# qo-100-env-sensors.net
KiCad netlist of a schematic drawn in EAGLE
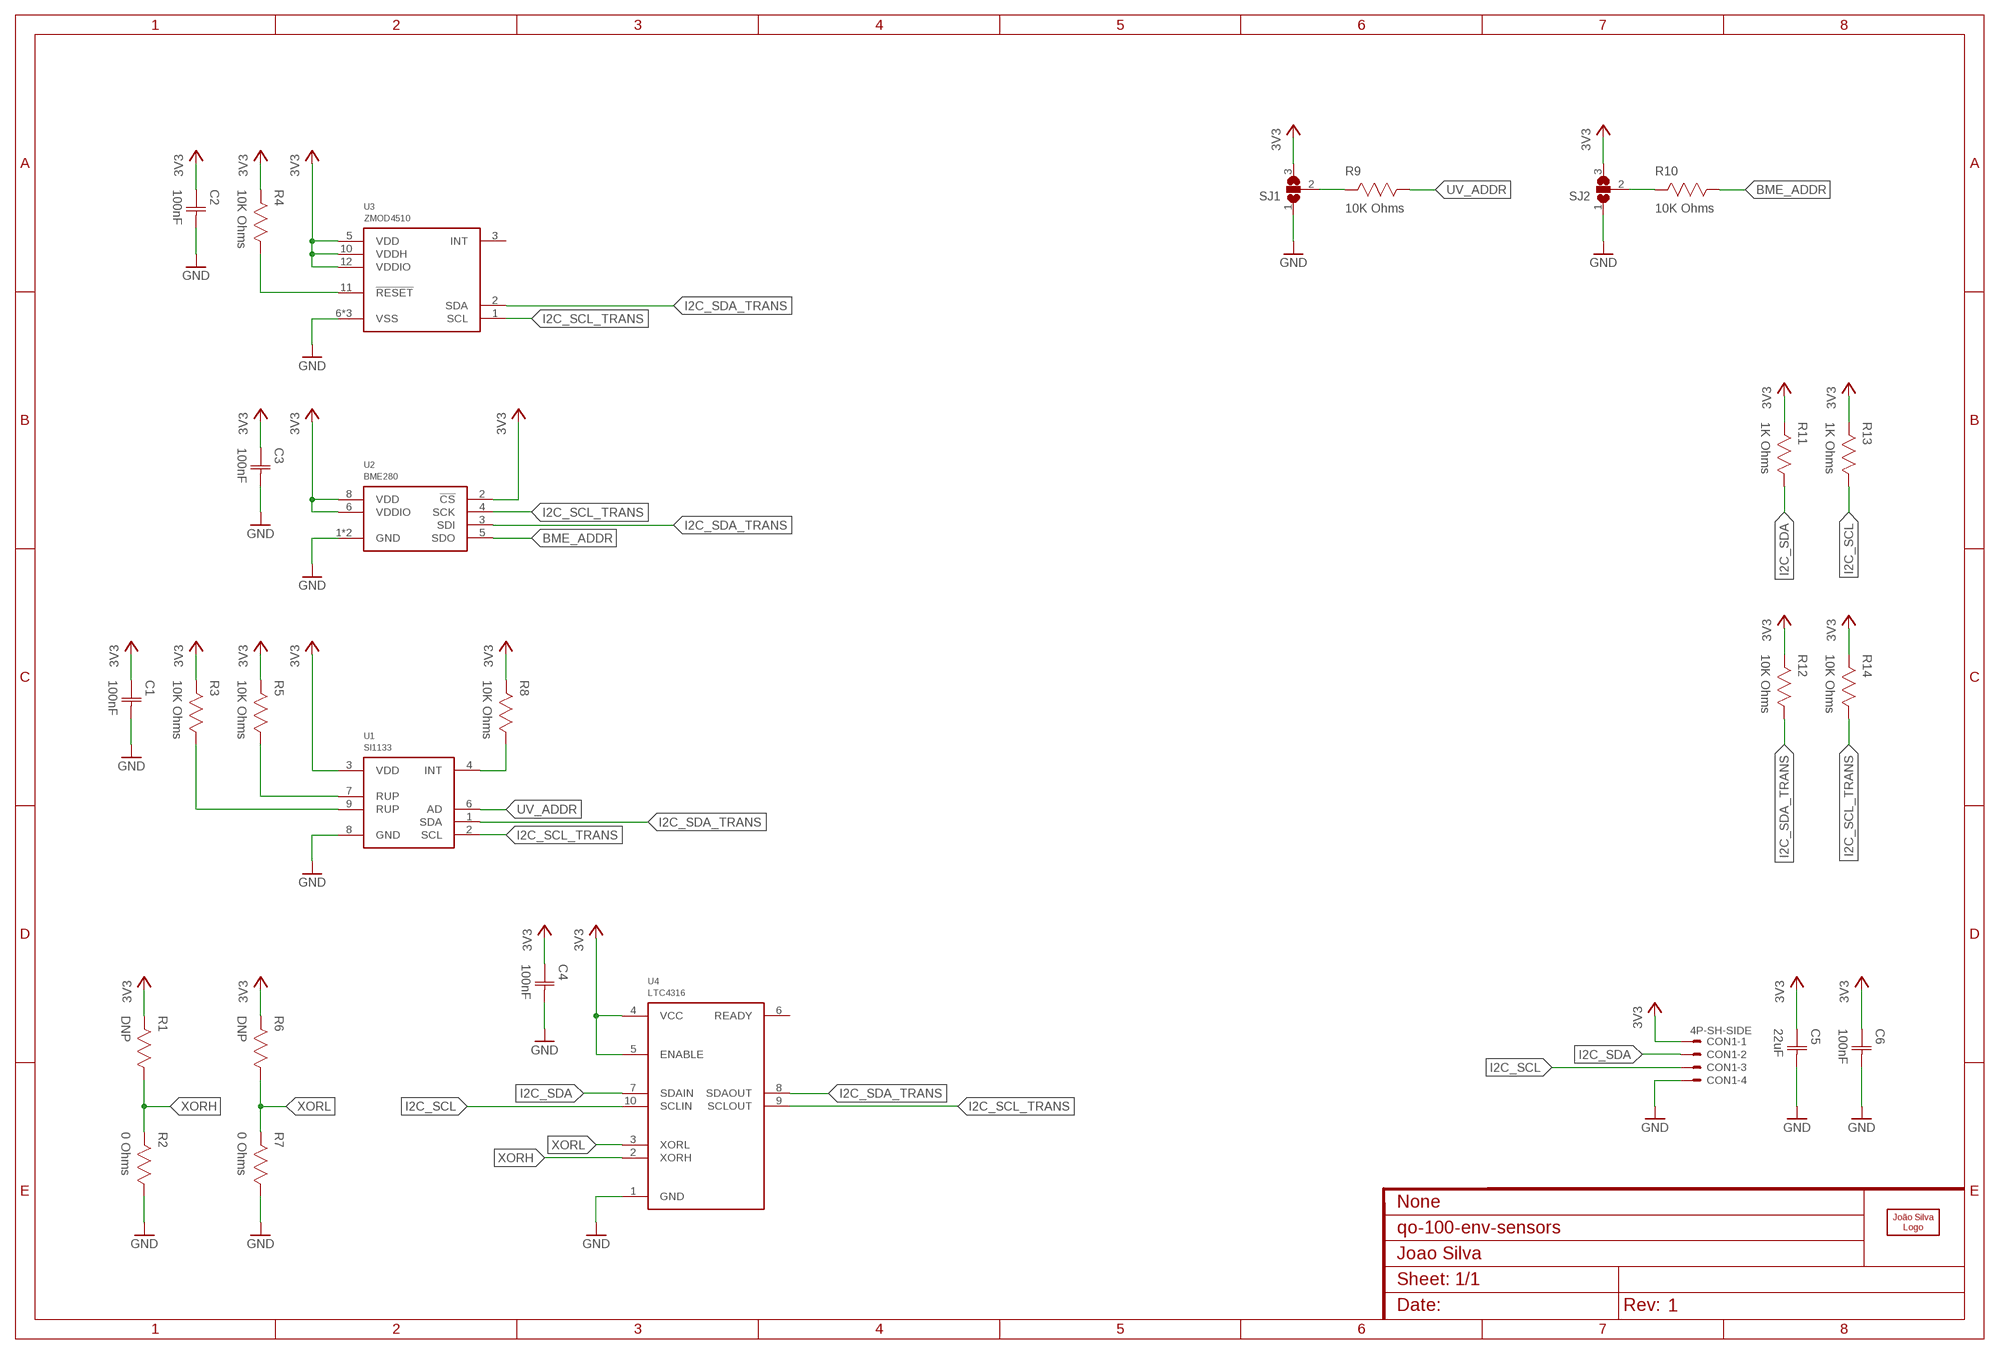
[diagram p0: schematic, sheet 1]

(export (version "E")
  (design (tool "Eeschema 10.0.6"))
  (components
    (comp (ref "C1")
      (value "100nF")
      (footprint "eagle-import:CAP0603")
      (libsource (lib "eagle-import") (part "CAPACITOR-0603"))
    )
    (comp (ref "C2")
      (value "100nF")
      (footprint "eagle-import:CAP0603")
      (libsource (lib "eagle-import") (part "CAPACITOR-0603"))
    )
    (comp (ref "C3")
      (value "100nF")
      (footprint "eagle-import:CAP0603")
      (libsource (lib "eagle-import") (part "CAPACITOR-0603"))
    )
    (comp (ref "C4")
      (value "100nF")
      (footprint "eagle-import:CAP0603")
      (libsource (lib "eagle-import") (part "CAPACITOR-0603"))
    )
    (comp (ref "C5")
      (value "22uF")
      (footprint "eagle-import:CAP1206")
      (libsource (lib "eagle-import") (part "CAPACITOR-1206"))
    )
    (comp (ref "C6")
      (value "100nF")
      (footprint "eagle-import:CAP0603")
      (libsource (lib "eagle-import") (part "CAPACITOR-0603"))
    )
    (comp (ref "CON1")
      (value "4P-SH-SIDE")
      (footprint "eagle-import:SH-04-SIDE")
      (libsource (lib "eagle-import") (part "4P-SH-SIDE"))
    )
    (comp (ref "LOGO1")
      (value "JS-5MM")
      (footprint "eagle-import:JS_5MM")
      (libsource (lib "eagle-import") (part "JS-5MM"))
    )
    (comp (ref "R1")
      (value "DNP")
      (footprint "eagle-import:RES0603")
      (libsource (lib "eagle-import") (part "RESISTOR-0603"))
    )
    (comp (ref "R2")
      (value "0 Ohms")
      (footprint "eagle-import:RES0603")
      (libsource (lib "eagle-import") (part "RESISTOR-0603"))
    )
    (comp (ref "R3")
      (value "10K Ohms")
      (footprint "eagle-import:RES0603")
      (libsource (lib "eagle-import") (part "RESISTOR-0603"))
    )
    (comp (ref "R4")
      (value "10K Ohms")
      (footprint "eagle-import:RES0603")
      (libsource (lib "eagle-import") (part "RESISTOR-0603"))
    )
    (comp (ref "R5")
      (value "10K Ohms")
      (footprint "eagle-import:RES0603")
      (libsource (lib "eagle-import") (part "RESISTOR-0603"))
    )
    (comp (ref "R6")
      (value "DNP")
      (footprint "eagle-import:RES0603")
      (libsource (lib "eagle-import") (part "RESISTOR-0603"))
    )
    (comp (ref "R7")
      (value "0 Ohms")
      (footprint "eagle-import:RES0603")
      (libsource (lib "eagle-import") (part "RESISTOR-0603"))
    )
    (comp (ref "R8")
      (value "10K Ohms")
      (footprint "eagle-import:RES0603")
      (libsource (lib "eagle-import") (part "RESISTOR-0603"))
    )
    (comp (ref "R9")
      (value "10K Ohms")
      (footprint "eagle-import:RES0603")
      (libsource (lib "eagle-import") (part "RESISTOR-0603"))
    )
    (comp (ref "R10")
      (value "10K Ohms")
      (footprint "eagle-import:RES0603")
      (libsource (lib "eagle-import") (part "RESISTOR-0603"))
    )
    (comp (ref "R11")
      (value "1K Ohms")
      (footprint "eagle-import:RES0603")
      (libsource (lib "eagle-import") (part "RESISTOR-0603"))
    )
    (comp (ref "R12")
      (value "10K Ohms")
      (footprint "eagle-import:RES0603")
      (libsource (lib "eagle-import") (part "RESISTOR-0603"))
    )
    (comp (ref "R13")
      (value "1K Ohms")
      (footprint "eagle-import:RES0603")
      (libsource (lib "eagle-import") (part "RESISTOR-0603"))
    )
    (comp (ref "R14")
      (value "10K Ohms")
      (footprint "eagle-import:RES0603")
      (libsource (lib "eagle-import") (part "RESISTOR-0603"))
    )
    (comp (ref "SJ1")
      (value "SJ2S")
      (footprint "eagle-import:SJ2_S")
      (libsource (lib "eagle-import") (part "SJ2S"))
    )
    (comp (ref "SJ2")
      (value "SJ2S")
      (footprint "eagle-import:SJ2_S")
      (libsource (lib "eagle-import") (part "SJ2S"))
    )
    (comp (ref "U1")
      (value "SI1133")
      (footprint "eagle-import:DFN10")
      (libsource (lib "eagle-import") (part "SI1133"))
    )
    (comp (ref "U2")
      (value "BME280")
      (footprint "eagle-import:BME280")
      (libsource (lib "eagle-import") (part "BME280"))
    )
    (comp (ref "U3")
      (value "ZMOD4510")
      (footprint "eagle-import:LGA12")
      (libsource (lib "eagle-import") (part "ZMOD4105"))
    )
    (comp (ref "U4")
      (value "LTC4316")
      (footprint "eagle-import:MSOP10")
      (libsource (lib "eagle-import") (part "LTC4316"))
    )
  )
  (nets
    (net (code "1") (name "3V3") (class "Default")
      (node (ref "C1") (pin "1") (pinfunction "C1_1") (pintype "passive"))
      (node (ref "C2") (pin "1") (pinfunction "C1_1") (pintype "passive"))
      (node (ref "C3") (pin "1") (pinfunction "C1_1") (pintype "passive"))
      (node (ref "C4") (pin "1") (pinfunction "C1_1") (pintype "passive"))
      (node (ref "C5") (pin "1") (pinfunction "C1_1") (pintype "passive"))
      (node (ref "C6") (pin "1") (pinfunction "C1_1") (pintype "passive"))
      (node (ref "CON1") (pin "1") (pinfunction "S_1") (pintype "passive"))
      (node (ref "R1") (pin "2") (pinfunction "2_2") (pintype "passive"))
      (node (ref "R11") (pin "2") (pinfunction "2_2") (pintype "passive"))
      (node (ref "R12") (pin "2") (pinfunction "2_2") (pintype "passive"))
      (node (ref "R13") (pin "2") (pinfunction "2_2") (pintype "passive"))
      (node (ref "R14") (pin "2") (pinfunction "2_2") (pintype "passive"))
      (node (ref "R3") (pin "2") (pinfunction "2_2") (pintype "passive"))
      (node (ref "R4") (pin "2") (pinfunction "2_2") (pintype "passive"))
      (node (ref "R5") (pin "2") (pinfunction "2_2") (pintype "passive"))
      (node (ref "R6") (pin "2") (pinfunction "2_2") (pintype "passive"))
      (node (ref "R8") (pin "2") (pinfunction "2_2") (pintype "passive"))
      (node (ref "SJ1") (pin "3") (pinfunction "3_3") (pintype "passive"))
      (node (ref "SJ2") (pin "3") (pinfunction "3_3") (pintype "passive"))
      (node (ref "U1") (pin "3") (pinfunction "VDD_3") (pintype "bidirectional"))
      (node (ref "U2") (pin "2") (pinfunction "~{CS}_2") (pintype "input"))
      (node (ref "U2") (pin "6") (pinfunction "VDDIO_6") (pintype "power_in"))
      (node (ref "U2") (pin "8") (pinfunction "VDD_8") (pintype "power_in"))
      (node (ref "U3") (pin "10") (pinfunction "VDDH_10") (pintype "bidirectional"))
      (node (ref "U3") (pin "12") (pinfunction "VDDIO_12") (pintype "bidirectional"))
      (node (ref "U3") (pin "5") (pinfunction "VDD_5") (pintype "bidirectional"))
      (node (ref "U4") (pin "4") (pinfunction "VCC_4") (pintype "bidirectional"))
      (node (ref "U4") (pin "5") (pinfunction "ENABLE_5") (pintype "bidirectional"))
    )
    (net (code "2") (name "BME_ADDR") (class "Default")
      (node (ref "R10") (pin "1") (pinfunction "1_1") (pintype "passive"))
      (node (ref "U2") (pin "5") (pinfunction "SDO_5") (pintype "input"))
    )
    (net (code "3") (name "GND") (class "Default")
      (node (ref "C1") (pin "2") (pinfunction "C2_2") (pintype "passive"))
      (node (ref "C2") (pin "2") (pinfunction "C2_2") (pintype "passive"))
      (node (ref "C3") (pin "2") (pinfunction "C2_2") (pintype "passive"))
      (node (ref "C4") (pin "2") (pinfunction "C2_2") (pintype "passive"))
      (node (ref "C5") (pin "2") (pinfunction "C2_2") (pintype "passive"))
      (node (ref "C6") (pin "2") (pinfunction "C2_2") (pintype "passive"))
      (node (ref "CON1") (pin "4") (pinfunction "S_4") (pintype "passive"))
      (node (ref "R2") (pin "1") (pinfunction "1_1") (pintype "passive"))
      (node (ref "R7") (pin "1") (pinfunction "1_1") (pintype "passive"))
      (node (ref "SJ1") (pin "1") (pinfunction "1_1") (pintype "passive"))
      (node (ref "SJ2") (pin "1") (pinfunction "1_1") (pintype "passive"))
      (node (ref "U1") (pin "8") (pinfunction "GND_8") (pintype "bidirectional"))
      (node (ref "U2") (pin "1") (pinfunction "GND_1") (pintype "power_in"))
      (node (ref "U2") (pin "7") (pinfunction "GND_7") (pintype "power_in"))
      (node (ref "U3") (pin "6") (pinfunction "VSS_6") (pintype "bidirectional"))
      (node (ref "U3") (pin "7") (pinfunction "VSS_7") (pintype "bidirectional"))
      (node (ref "U3") (pin "9") (pinfunction "VSS_9") (pintype "bidirectional"))
      (node (ref "U4") (pin "1") (pinfunction "GND_1") (pintype "bidirectional"))
    )
    (net (code "4") (name "I2C_SCL") (class "Default")
      (node (ref "CON1") (pin "3") (pinfunction "S_3") (pintype "passive"))
      (node (ref "R13") (pin "1") (pinfunction "1_1") (pintype "passive"))
      (node (ref "U4") (pin "10") (pinfunction "SCLIN_10") (pintype "bidirectional"))
    )
    (net (code "5") (name "I2C_SCL_TRANS") (class "Default")
      (node (ref "R14") (pin "1") (pinfunction "1_1") (pintype "passive"))
      (node (ref "U1") (pin "2") (pinfunction "SCL_2") (pintype "bidirectional"))
      (node (ref "U2") (pin "4") (pinfunction "SCK_4") (pintype "bidirectional"))
      (node (ref "U3") (pin "1") (pinfunction "SCL_1") (pintype "bidirectional"))
      (node (ref "U4") (pin "9") (pinfunction "SCLOUT_9") (pintype "bidirectional"))
    )
    (net (code "6") (name "I2C_SDA") (class "Default")
      (node (ref "CON1") (pin "2") (pinfunction "S_2") (pintype "passive"))
      (node (ref "R11") (pin "1") (pinfunction "1_1") (pintype "passive"))
      (node (ref "U4") (pin "7") (pinfunction "SDAIN_7") (pintype "bidirectional"))
    )
    (net (code "7") (name "I2C_SDA_TRANS") (class "Default")
      (node (ref "R12") (pin "1") (pinfunction "1_1") (pintype "passive"))
      (node (ref "U1") (pin "1") (pinfunction "SDA_1") (pintype "bidirectional"))
      (node (ref "U2") (pin "3") (pinfunction "SDI_3") (pintype "bidirectional"))
      (node (ref "U3") (pin "2") (pinfunction "SDA_2") (pintype "bidirectional"))
      (node (ref "U4") (pin "8") (pinfunction "SDAOUT_8") (pintype "bidirectional"))
    )
    (net (code "8") (name "Net-(R3-Pad1)") (class "Default")
      (node (ref "R3") (pin "1") (pinfunction "1_1") (pintype "passive"))
      (node (ref "U1") (pin "9") (pinfunction "RUP_9") (pintype "bidirectional"))
    )
    (net (code "9") (name "Net-(R5-Pad1)") (class "Default")
      (node (ref "R5") (pin "1") (pinfunction "1_1") (pintype "passive"))
      (node (ref "U1") (pin "7") (pinfunction "RUP_7") (pintype "bidirectional"))
    )
    (net (code "10") (name "Net-(R9-Pad2)") (class "Default")
      (node (ref "R9") (pin "2") (pinfunction "2_2") (pintype "passive"))
      (node (ref "SJ1") (pin "2") (pinfunction "2_2") (pintype "passive"))
    )
    (net (code "11") (name "Net-(R10-Pad2)") (class "Default")
      (node (ref "R10") (pin "2") (pinfunction "2_2") (pintype "passive"))
      (node (ref "SJ2") (pin "2") (pinfunction "2_2") (pintype "passive"))
    )
    (net (code "12") (name "Net-(U1-INT)") (class "Default")
      (node (ref "R8") (pin "1") (pinfunction "1_1") (pintype "passive"))
      (node (ref "U1") (pin "4") (pinfunction "INT_4") (pintype "bidirectional"))
    )
    (net (code "13") (name "Net-(U3-~{RESET})") (class "Default")
      (node (ref "R4") (pin "1") (pinfunction "1_1") (pintype "passive"))
      (node (ref "U3") (pin "11") (pinfunction "~{RESET}_11") (pintype "bidirectional"))
    )
    (net (code "14") (name "UV_ADDR") (class "Default")
      (node (ref "R9") (pin "1") (pinfunction "1_1") (pintype "passive"))
      (node (ref "U1") (pin "6") (pinfunction "AD_6") (pintype "bidirectional"))
    )
    (net (code "15") (name "XORH") (class "Default")
      (node (ref "R1") (pin "1") (pinfunction "1_1") (pintype "passive"))
      (node (ref "R2") (pin "2") (pinfunction "2_2") (pintype "passive"))
      (node (ref "U4") (pin "2") (pinfunction "XORH_2") (pintype "bidirectional"))
    )
    (net (code "16") (name "XORL") (class "Default")
      (node (ref "R6") (pin "1") (pinfunction "1_1") (pintype "passive"))
      (node (ref "R7") (pin "2") (pinfunction "2_2") (pintype "passive"))
      (node (ref "U4") (pin "3") (pinfunction "XORL_3") (pintype "bidirectional"))
    )
    (net (code "17") (name "unconnected-(U3-INT-Pad3)") (class "Default")
      (node (ref "U3") (pin "3") (pinfunction "INT_3") (pintype "bidirectional"))
    )
    (net (code "18") (name "unconnected-(U4-READY-Pad6)") (class "Default")
      (node (ref "U4") (pin "6") (pinfunction "READY_6") (pintype "bidirectional"))
    )
  )
)
